# Sheet1.net
KiCad netlist of a schematic drawn in Altium Designer
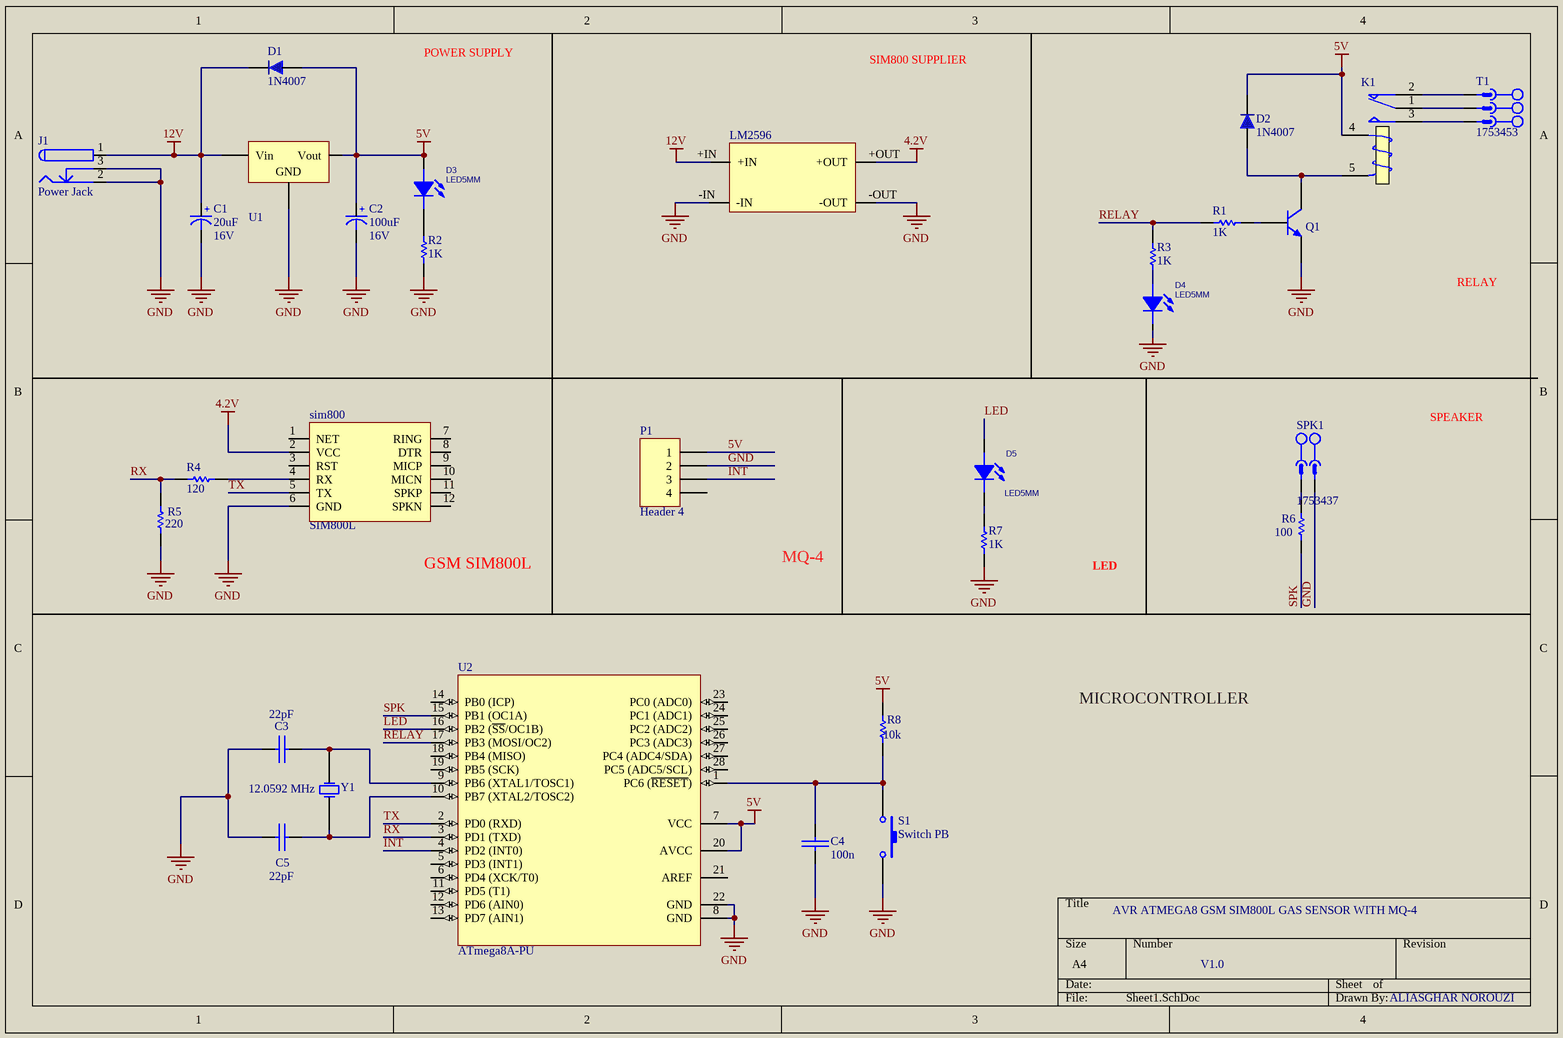
[diagram p0: Sheet1.SchDoc]

(export (version "E")
  (design (tool "Eeschema 10.0.6"))
  (components
    (comp (ref "C1")
      (value "20uF")
      (footprint "cap 01")
      (description "Polar Capacitor")
      (fields (field (name "VOLTAGE") "16V") (field (name "DESIGNER") "Saeid Jorablo"))
      (libsource (lib "General 2") (part "Cap-Polar"))
    )
    (comp (ref "C2")
      (value "100uF")
      (footprint "cap 01")
      (description "Polar Capacitor")
      (fields (field (name "VOLTAGE") "16V") (field (name "DESIGNER") "Saeid Jorablo"))
      (libsource (lib "General 2") (part "Cap-Polar"))
    )
    (comp (ref "C3")
      (value "22pF")
      (footprint "Cap - 100nF")
      (description "Bipolar Capacitor")
      (fields (field (name "VOLTAGE") "100V") (field (name "DESIGNER") "Saeid Jorablo"))
      (libsource (lib "General 2") (part "Cap-Bipolar"))
    )
    (comp (ref "C4")
      (value "100n")
      (footprint "Cap - 100nF")
      (description "Bipolar Capacitor")
      (fields (field (name "VOLTAGE") "100V") (field (name "DESIGNER") "Saeid Jorablo"))
      (libsource (lib "General 2") (part "Cap-Bipolar"))
    )
    (comp (ref "C5")
      (value "22pF")
      (footprint "Cap - 100nF")
      (description "Bipolar Capacitor")
      (fields (field (name "VOLTAGE") "100V") (field (name "DESIGNER") "Saeid Jorablo"))
      (libsource (lib "General 2") (part "Cap-Bipolar"))
    )
    (comp (ref "D1")
      (value "1N4007")
      (footprint "DO 35")
      (description "DIODE GEN PURP 100V 200MA DO35")
      (fields (field (name "PUBLISHER") "Abbas Basereh"))
      (libsource (lib "General 1") (part "1N4148"))
    )
    (comp (ref "D2")
      (value "1N4007")
      (footprint "DO 35")
      (description "DIODE GEN PURP 100V 200MA DO35")
      (fields (field (name "PUBLISHER") "Abbas Basereh"))
      (libsource (lib "General 1") (part "1N4148"))
    )
    (comp (ref "D3")
      (value "LED5MM")
      (footprint "LED5MM_YELLOW")
      (description "LED LIGHTING")
      (fields (field (name "DESIGNER") "Abbas Basereh"))
      (libsource (lib "General 1") (part "LED5MM"))
    )
    (comp (ref "D4")
      (value "LED5MM")
      (footprint "LED5MM_YELLOW")
      (description "LED LIGHTING")
      (fields (field (name "DESIGNER") "Abbas Basereh"))
      (libsource (lib "General 1") (part "LED5MM"))
    )
    (comp (ref "D5")
      (value "LED5MM")
      (footprint "LED5MM_BLUE")
      (description "LED LIGHTING")
      (fields (field (name "DESIGNER") "Abbas Basereh"))
      (libsource (lib "General 1") (part "LED5MM"))
    )
    (comp (ref "J1")
      (value "Power Jack")
      (footprint "Power Jack")
      (fields (field (name "DESIGNER") "Saeid Jorablo"))
      (libsource (lib "General 2") (part "Power Jack"))
    )
    (comp (ref "K1")
      (value "~")
      (footprint "Relay 18.85x15.35x15.70")
      (description "Single-Pole Dual-Throw Relay")
      (fields (field (name "DESIGNER") "Abbas Basereh"))
      (libsource (lib "General 1") (part "Relay_SPDT"))
    )
    (comp (ref "LM2596") (value "LM2596") (footprint "LM2696") (libsource (lib "Schlib1") (part "LM2596")))
    (comp (ref "P1")
      (value "Header 4")
      (footprint "HDR1X4")
      (description "Header, 4-Pin")
      (fields (field (name "PUBLISHER") "Altium Limited"))
      (libsource (lib "Altium") (part "Header 4"))
    )
    (comp (ref "Q1")
      (value "BC547")
      (footprint "TO-92 BENT")
      (description "NPN Transistor")
      (fields (field (name "DESIGNER") "Abbas Basereh"))
      (libsource (lib "General 1") (part "BC547"))
    )
    (comp (ref "R1")
      (value "1K")
      (footprint "Axial 0_25 W, 0_4 IN LEAD PITCH")
      (description "RES Axial 0.25W")
      (fields (field (name "DESIGNER") "Abbas Basereh"))
      (libsource (lib "General 1") (part "RES Axial 0.25W"))
    )
    (comp (ref "R2")
      (value "1K")
      (footprint "Axial 0_25 W, 0_4 IN LEAD PITCH")
      (description "RES Axial 0.25W")
      (fields (field (name "DESIGNER") "Abbas Basereh"))
      (libsource (lib "General 1") (part "RES Axial 0.25W"))
    )
    (comp (ref "R3")
      (value "1K")
      (footprint "Axial 0_25 W, 0_4 IN LEAD PITCH")
      (description "RES Axial 0.25W")
      (fields (field (name "DESIGNER") "Abbas Basereh"))
      (libsource (lib "General 1") (part "RES Axial 0.25W"))
    )
    (comp (ref "R4")
      (value "120")
      (footprint "Axial 0_25 W, 0_4 IN LEAD PITCH")
      (description "RES Axial 0.25W")
      (fields (field (name "DESIGNER") "Abbas Basereh"))
      (libsource (lib "General 1") (part "RES Axial 0.25W"))
    )
    (comp (ref "R5")
      (value "220")
      (footprint "Axial 0_25 W, 0_4 IN LEAD PITCH")
      (description "RES Axial 0.25W")
      (fields (field (name "DESIGNER") "Abbas Basereh"))
      (libsource (lib "General 1") (part "RES Axial 0.25W"))
    )
    (comp (ref "R6")
      (value "100")
      (footprint "Axial 0_25 W, 0_4 IN LEAD PITCH")
      (description "RES Axial 0.25W")
      (fields (field (name "DESIGNER") "Abbas Basereh"))
      (libsource (lib "General 1") (part "RES Axial 0.25W"))
    )
    (comp (ref "R7")
      (value "1K")
      (footprint "Axial 0_25 W, 0_4 IN LEAD PITCH")
      (description "RES Axial 0.25W")
      (fields (field (name "DESIGNER") "Abbas Basereh"))
      (libsource (lib "General 1") (part "RES Axial 0.25W"))
    )
    (comp (ref "R8")
      (value "10k")
      (footprint "Axial 0_25 W, 0_4 IN LEAD PITCH")
      (description "RES Axial 0.25W")
      (fields (field (name "DESIGNER") "Abbas Basereh"))
      (libsource (lib "General 1") (part "RES Axial 0.25W"))
    )
    (comp (ref "S1")
      (value "Switch PB")
      (footprint "Switch - Push to On")
      (description "Push Button Switch")
      (libsource (lib "General 2") (part "Switch PB"))
    )
    (comp (ref "sim800")
      (value "sim800l")
      (footprint "PCBComponent_1")
      (fields (field (name "NAME") "SIM800L"))
      (libsource (lib "Schlib1") (part "sim800l"))
    )
    (comp (ref "SPK1")
      (value "1753437")
      (footprint "MSTBV 2,5/2-G-5")
      (description "2 Pitch: 5 mm Color: green Contact surface: Tin Assembly")
      (fields
        (field (name "MANUFACTURER") "PHOENIX CONTACT")
        (field (name "VOLTAGE") "320 V")
        (field (name "DESIGNER") "ABBAS BASEREH")
      )
      (libsource (lib "General 1") (part "CON_Phoenix_MSTBV_02"))
    )
    (comp (ref "T1")
      (value "1753453")
      (footprint "MSTBV 2,5/3-G-5")
      (description "3 Pitch: 5 mm Color: green Contact surface: Tin Assembly")
      (fields
        (field (name "MANUFACTURER") "PHOENIX CONTACT")
        (field (name "VOLTAGE") "320 V")
        (field (name "DESIGNER") "ABBAS BASEREH")
      )
      (libsource (lib "General 1") (part "CON_Phoenix_MSTBV_03"))
    )
    (comp (ref "U1")
      (value "L7805CV")
      (footprint "TO-220 AB")
      (description "Linear Voltage Regulator IC Positive FIXED")
      (fields (field (name "MANUFACTURER") "STMicroelectronics") (field (name "DESIGNER") "Abbas Basereh"))
      (libsource (lib "General 1") (part "L7805CV-Linear Voltage Regulator IC Positive 1 Output 5V 1.5A TO-220AB"))
    )
    (comp (ref "U2")
      (value "ATmega8A-PU")
      (footprint "28P3")
      (fields (field (name "PUBLISHER") "Abbas Basereh"))
      (libsource (lib "General 1") (part "ATmega8A-PU"))
    )
    (comp (ref "Y1")
      (value "12.0592 MHz")
      (footprint "CRYSTAL Small")
      (description "XTAL Crystal")
      (fields (field (name "DESIGNER") "ABBAS BASEREH"))
      (libsource (lib "General 1") (part "XTAL_Crystal"))
    )
  )
  (nets
    (net (code "1") (name "/INT") (class "Default")
      (node (ref "P1") (pin "3") (pinfunction "3_3") (pintype "passive"))
      (node (ref "U2") (pin "4") (pinfunction "PD2_(INT0)_4") (pintype "bidirectional"))
    )
    (net (code "2") (name "/LED") (class "Default")
      (node (ref "D5") (pin "1") (pinfunction "ANODE_1") (pintype "passive"))
      (node (ref "U2") (pin "16") (pinfunction "PB2_(~{SS}/OC1B)_16") (pintype "bidirectional"))
    )
    (net (code "3") (name "/RELAY") (class "Default")
      (node (ref "R1") (pin "2") (pinfunction "2_2") (pintype "passive"))
      (node (ref "R3") (pin "2") (pinfunction "2_2") (pintype "passive"))
      (node (ref "U2") (pin "17") (pinfunction "PB3_(MOSI/OC2)_17") (pintype "bidirectional"))
    )
    (net (code "4") (name "/RX") (class "Default")
      (node (ref "R4") (pin "1") (pinfunction "1_1") (pintype "passive"))
      (node (ref "R5") (pin "1") (pinfunction "1_1") (pintype "passive"))
      (node (ref "U2") (pin "3") (pinfunction "PD1_(TXD)_3") (pintype "bidirectional"))
    )
    (net (code "5") (name "/SPK") (class "Default")
      (node (ref "R6") (pin "1") (pinfunction "1_1") (pintype "passive"))
      (node (ref "U2") (pin "15") (pinfunction "PB1_(OC1A)_15") (pintype "bidirectional"))
    )
    (net (code "6") (name "/TX") (class "Default")
      (node (ref "U2") (pin "2") (pinfunction "PD0_(RXD)_2") (pintype "bidirectional"))
      (node (ref "sim800") (pin "5") (pinfunction "TX_5") (pintype "passive"))
    )
    (net (code "7") (name "4.2V") (class "Default")
      (node (ref "LM2596") (pin "+OUT") (pinfunction "+OUT_+OUT") (pintype "passive"))
      (node (ref "sim800") (pin "2") (pinfunction "VCC_2") (pintype "passive"))
    )
    (net (code "8") (name "5V") (class "Default")
      (node (ref "C2") (pin "1") (pinfunction "+_1") (pintype "passive"))
      (node (ref "D1") (pin "1") (pintype "passive"))
      (node (ref "D2") (pin "2") (pintype "passive"))
      (node (ref "D3") (pin "1") (pinfunction "ANODE_1") (pintype "passive"))
      (node (ref "K1") (pin "4") (pinfunction "T1_4") (pintype "passive"))
      (node (ref "P1") (pin "1") (pinfunction "1_1") (pintype "passive"))
      (node (ref "R8") (pin "2") (pinfunction "2_2") (pintype "passive"))
      (node (ref "U1") (pin "3") (pinfunction "Vout_3") (pintype "passive"))
      (node (ref "U2") (pin "20") (pinfunction "AVCC_20") (pintype "power_in"))
      (node (ref "U2") (pin "7") (pinfunction "VCC_7") (pintype "power_in"))
    )
    (net (code "9") (name "12V") (class "Default")
      (node (ref "C1") (pin "1") (pinfunction "+_1") (pintype "passive"))
      (node (ref "D1") (pin "2") (pintype "passive"))
      (node (ref "J1") (pin "1") (pinfunction "1_1") (pintype "power_in"))
      (node (ref "LM2596") (pin "+IN") (pinfunction "+IN_+IN") (pintype "passive"))
      (node (ref "U1") (pin "1") (pinfunction "Vin_1") (pintype "passive"))
    )
    (net (code "10") (name "GND") (class "Default")
      (node (ref "C1") (pin "2") (pinfunction "-_2") (pintype "passive"))
      (node (ref "C2") (pin "2") (pinfunction "-_2") (pintype "passive"))
      (node (ref "C3") (pin "2") (pinfunction "-_2") (pintype "passive"))
      (node (ref "C4") (pin "2") (pinfunction "-_2") (pintype "passive"))
      (node (ref "C5") (pin "1") (pinfunction "+_1") (pintype "passive"))
      (node (ref "D4") (pin "2") (pinfunction "CATHODE_2") (pintype "passive"))
      (node (ref "J1") (pin "2") (pinfunction "2_2") (pintype "power_in"))
      (node (ref "J1") (pin "3") (pinfunction "3_3") (pintype "power_in"))
      (node (ref "LM2596") (pin "-IN") (pinfunction "-IN_-IN") (pintype "passive"))
      (node (ref "LM2596") (pin "-OUT") (pinfunction "-OUT_-OUT") (pintype "passive"))
      (node (ref "P1") (pin "2") (pinfunction "2_2") (pintype "passive"))
      (node (ref "Q1") (pin "3") (pinfunction "E_3") (pintype "passive"))
      (node (ref "R2") (pin "1") (pinfunction "1_1") (pintype "passive"))
      (node (ref "R5") (pin "2") (pinfunction "2_2") (pintype "passive"))
      (node (ref "R7") (pin "1") (pinfunction "1_1") (pintype "passive"))
      (node (ref "S1") (pin "2") (pinfunction "2_2") (pintype "passive"))
      (node (ref "SPK1") (pin "2") (pinfunction "2_2") (pintype "passive"))
      (node (ref "U1") (pin "2") (pinfunction "GND_2") (pintype "passive"))
      (node (ref "U2") (pin "22") (pinfunction "GND_22") (pintype "power_in"))
      (node (ref "U2") (pin "8") (pinfunction "GND_8") (pintype "power_in"))
      (node (ref "sim800") (pin "6") (pinfunction "GND_6") (pintype "passive"))
    )
    (net (code "11") (name "Net-(C3-+)") (class "Default")
      (node (ref "C3") (pin "1") (pinfunction "+_1") (pintype "passive"))
      (node (ref "U2") (pin "9") (pinfunction "PB6_(XTAL1/TOSC1)_9") (pintype "bidirectional"))
      (node (ref "Y1") (pin "1") (pinfunction "OSC1_1") (pintype "passive"))
    )
    (net (code "12") (name "Net-(C4-+)") (class "Default")
      (node (ref "C4") (pin "1") (pinfunction "+_1") (pintype "passive"))
      (node (ref "R8") (pin "1") (pinfunction "1_1") (pintype "passive"))
      (node (ref "S1") (pin "1") (pinfunction "1_1") (pintype "passive"))
      (node (ref "U2") (pin "1") (pinfunction "PC6_(~{RESET})_1") (pintype "bidirectional"))
    )
    (net (code "13") (name "Net-(C5--)") (class "Default")
      (node (ref "C5") (pin "2") (pinfunction "-_2") (pintype "passive"))
      (node (ref "U2") (pin "10") (pinfunction "PB7_(XTAL2/TOSC2)_10") (pintype "bidirectional"))
      (node (ref "Y1") (pin "2") (pinfunction "OSC2_2") (pintype "passive"))
    )
    (net (code "14") (name "Net-(D3-CATHODE)") (class "Default")
      (node (ref "D3") (pin "2") (pinfunction "CATHODE_2") (pintype "passive"))
      (node (ref "R2") (pin "2") (pinfunction "2_2") (pintype "passive"))
    )
    (net (code "15") (name "Net-(D4-ANODE)") (class "Default")
      (node (ref "D4") (pin "1") (pinfunction "ANODE_1") (pintype "passive"))
      (node (ref "R3") (pin "1") (pinfunction "1_1") (pintype "passive"))
    )
    (net (code "16") (name "Net-(D5-CATHODE)") (class "Default")
      (node (ref "D5") (pin "2") (pinfunction "CATHODE_2") (pintype "passive"))
      (node (ref "R7") (pin "2") (pinfunction "2_2") (pintype "passive"))
    )
    (net (code "17") (name "Net-(K1-COM)") (class "Default")
      (node (ref "K1") (pin "1") (pinfunction "COM_1") (pintype "passive"))
      (node (ref "T1") (pin "2") (pinfunction "2_2") (pintype "passive"))
    )
    (net (code "18") (name "Net-(K1-NC)") (class "Default")
      (node (ref "K1") (pin "2") (pinfunction "NC_2") (pintype "passive"))
      (node (ref "T1") (pin "1") (pinfunction "1_1") (pintype "passive"))
    )
    (net (code "19") (name "Net-(K1-NO)") (class "Default")
      (node (ref "K1") (pin "3") (pinfunction "NO_3") (pintype "passive"))
      (node (ref "T1") (pin "3") (pinfunction "3_3") (pintype "passive"))
    )
    (net (code "20") (name "Net-(K1-T2)") (class "Default")
      (node (ref "D2") (pin "1") (pintype "passive"))
      (node (ref "K1") (pin "5") (pinfunction "T2_5") (pintype "passive"))
      (node (ref "Q1") (pin "1") (pinfunction "C_1") (pintype "passive"))
    )
    (net (code "21") (name "Net-(Q1-B)") (class "Default")
      (node (ref "Q1") (pin "2") (pinfunction "B_2") (pintype "passive"))
      (node (ref "R1") (pin "1") (pinfunction "1_1") (pintype "passive"))
    )
    (net (code "22") (name "Net-(R6-Pad2)") (class "Default")
      (node (ref "R6") (pin "2") (pinfunction "2_2") (pintype "passive"))
      (node (ref "SPK1") (pin "1") (pinfunction "1_1") (pintype "passive"))
    )
    (net (code "23") (name "Net-(sim800-RX)") (class "Default")
      (node (ref "R4") (pin "2") (pinfunction "2_2") (pintype "passive"))
      (node (ref "sim800") (pin "4") (pinfunction "RX_4") (pintype "passive"))
    )
    (net (code "24") (name "unconnected-(P1-Pad4)") (class "Default")
      (node (ref "P1") (pin "4") (pinfunction "4_4") (pintype "passive"))
    )
    (net (code "25") (name "unconnected-(U2-AREF-Pad21)") (class "Default")
      (node (ref "U2") (pin "21") (pinfunction "AREF_21") (pintype "passive"))
    )
    (net (code "26") (name "unconnected-(U2-PB0_(ICP)-Pad14)") (class "Default")
      (node (ref "U2") (pin "14") (pinfunction "PB0_(ICP)_14") (pintype "bidirectional"))
    )
    (net (code "27") (name "unconnected-(U2-PB4_(MISO)-Pad18)") (class "Default")
      (node (ref "U2") (pin "18") (pinfunction "PB4_(MISO)_18") (pintype "bidirectional"))
    )
    (net (code "28") (name "unconnected-(U2-PB5_(SCK)-Pad19)") (class "Default")
      (node (ref "U2") (pin "19") (pinfunction "PB5_(SCK)_19") (pintype "bidirectional"))
    )
    (net (code "29") (name "unconnected-(U2-PC0_(ADC0)-Pad23)") (class "Default")
      (node (ref "U2") (pin "23") (pinfunction "PC0_(ADC0)_23") (pintype "bidirectional"))
    )
    (net (code "30") (name "unconnected-(U2-PC1_(ADC1)-Pad24)") (class "Default")
      (node (ref "U2") (pin "24") (pinfunction "PC1_(ADC1)_24") (pintype "bidirectional"))
    )
    (net (code "31") (name "unconnected-(U2-PC2_(ADC2)-Pad25)") (class "Default")
      (node (ref "U2") (pin "25") (pinfunction "PC2_(ADC2)_25") (pintype "bidirectional"))
    )
    (net (code "32") (name "unconnected-(U2-PC3_(ADC3)-Pad26)") (class "Default")
      (node (ref "U2") (pin "26") (pinfunction "PC3_(ADC3)_26") (pintype "bidirectional"))
    )
    (net (code "33") (name "unconnected-(U2-PC4_(ADC4{slash}SDA)-Pad27)") (class "Default")
      (node (ref "U2") (pin "27") (pinfunction "PC4_(ADC4/SDA)_27") (pintype "bidirectional"))
    )
    (net (code "34") (name "unconnected-(U2-PC5_(ADC5{slash}SCL)-Pad28)") (class "Default")
      (node (ref "U2") (pin "28") (pinfunction "PC5_(ADC5/SCL)_28") (pintype "bidirectional"))
    )
    (net (code "35") (name "unconnected-(U2-PD3_(INT1)-Pad5)") (class "Default")
      (node (ref "U2") (pin "5") (pinfunction "PD3_(INT1)_5") (pintype "bidirectional"))
    )
    (net (code "36") (name "unconnected-(U2-PD4_(XCK{slash}T0)-Pad6)") (class "Default")
      (node (ref "U2") (pin "6") (pinfunction "PD4_(XCK/T0)_6") (pintype "bidirectional"))
    )
    (net (code "37") (name "unconnected-(U2-PD5_(T1)-Pad11)") (class "Default")
      (node (ref "U2") (pin "11") (pinfunction "PD5_(T1)_11") (pintype "bidirectional"))
    )
    (net (code "38") (name "unconnected-(U2-PD6_(AIN0)-Pad12)") (class "Default")
      (node (ref "U2") (pin "12") (pinfunction "PD6_(AIN0)_12") (pintype "bidirectional"))
    )
    (net (code "39") (name "unconnected-(U2-PD7_(AIN1)-Pad13)") (class "Default")
      (node (ref "U2") (pin "13") (pinfunction "PD7_(AIN1)_13") (pintype "bidirectional"))
    )
    (net (code "40") (name "unconnected-(sim800-DTR-Pad8)") (class "Default")
      (node (ref "sim800") (pin "8") (pinfunction "DTR_8") (pintype "passive"))
    )
    (net (code "41") (name "unconnected-(sim800-MICN-Pad10)") (class "Default")
      (node (ref "sim800") (pin "10") (pinfunction "MICN_10") (pintype "passive"))
    )
    (net (code "42") (name "unconnected-(sim800-MICP-Pad9)") (class "Default")
      (node (ref "sim800") (pin "9") (pinfunction "MICP_9") (pintype "passive"))
    )
    (net (code "43") (name "unconnected-(sim800-NET-Pad1)") (class "Default")
      (node (ref "sim800") (pin "1") (pinfunction "NET_1") (pintype "passive"))
    )
    (net (code "44") (name "unconnected-(sim800-RING-Pad7)") (class "Default")
      (node (ref "sim800") (pin "7") (pinfunction "RING_7") (pintype "passive"))
    )
    (net (code "45") (name "unconnected-(sim800-RST-Pad3)") (class "Default")
      (node (ref "sim800") (pin "3") (pinfunction "RST_3") (pintype "passive"))
    )
    (net (code "46") (name "unconnected-(sim800-SPKN-Pad12)") (class "Default")
      (node (ref "sim800") (pin "12") (pinfunction "SPKN_12") (pintype "passive"))
    )
    (net (code "47") (name "unconnected-(sim800-SPKP-Pad11)") (class "Default")
      (node (ref "sim800") (pin "11") (pinfunction "SPKP_11") (pintype "passive"))
    )
  )
)
